# Sheet1.net
KiCad netlist of a schematic drawn in Altium Designer
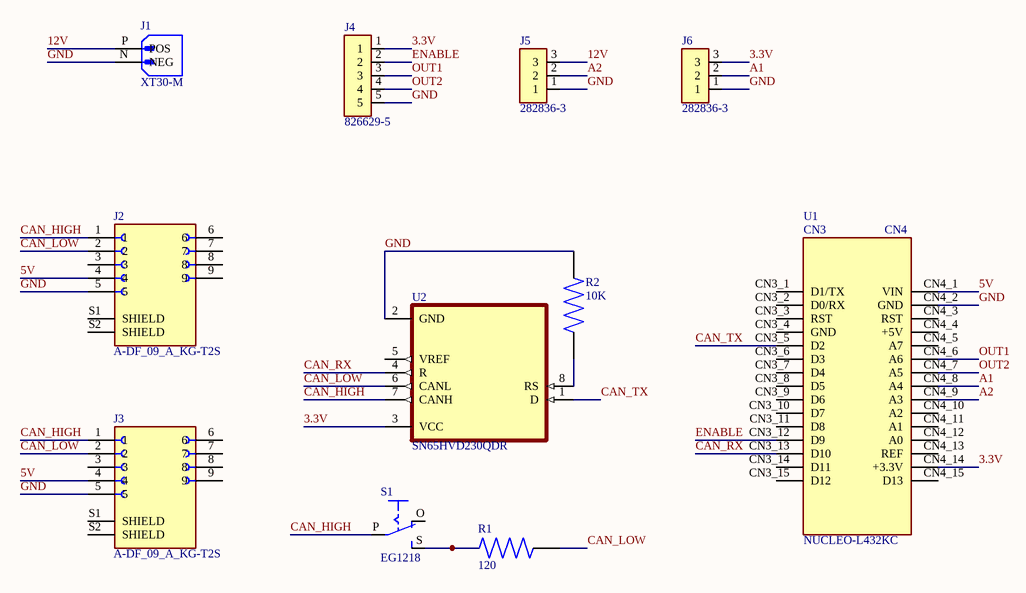
[diagram p0: Sheet1.SchDoc]

(export (version "E")
  (design (tool "Eeschema 10.0.6"))
  (components
    (comp (ref "J1")
      (value "XT30-M")
      (footprint "AMASS_XT60-M")
      (description "Plug; DC supply; XT60; male; PIN: 2; for cable; soldered; 30A; 500V")
      (fields (field (name "MP") "XT60-M") (field (name "MF") "AMASS"))
      (libsource (lib "XT30-M") (part "XT30-M"))
    )
    (comp (ref "J2")
      (value "A-DF_09_A_KG-T2S")
      (footprint "ASSMANN_A-DF_09_A_KG-T2S")
      (description "9 Position D-Sub Receptacle, Female Sockets Connector")
      (fields (field (name "MF") "Assmann WSW") (field (name "MP") "A-DF 09 A/KG-T2S"))
      (libsource (lib "A-DF_09_A_KG-T2S") (part "A-DF_09_A_KG-T2S"))
    )
    (comp (ref "J3")
      (value "A-DF_09_A_KG-T2S")
      (footprint "ASSMANN_A-DF_09_A_KG-T2S")
      (description "9 Position D-Sub Receptacle, Female Sockets Connector")
      (fields (field (name "MF") "Assmann WSW") (field (name "MP") "A-DF 09 A/KG-T2S"))
      (libsource (lib "A-DF_09_A_KG-T2S") (part "A-DF_09_A_KG-T2S"))
    )
    (comp (ref "J4")
      (value "826629-5")
      (footprint "TE_826629-5")
      (description "Board-To-Board Connector, AMPMODU MOD II Series, Through Hole, Header, 5, 2.54 mm")
      (fields (field (name "MF") "TE Connectivity"))
      (libsource (lib "826629-5") (part "826629-5"))
    )
    (comp (ref "J5")
      (value "282836-3")
      (footprint "TE_282836-3")
      (description "TERM BLOCK 3POS SIDE ENTRY 5MM")
      (libsource (lib "282836-3") (part "282836-3"))
    )
    (comp (ref "J6")
      (value "282836-3")
      (footprint "TE_282836-3")
      (description "TERM BLOCK 3POS SIDE ENTRY 5MM")
      (libsource (lib "282836-3") (part "282836-3"))
    )
    (comp (ref "R1")
      (value "120")
      (footprint "RESC3216X65N")
      (fields (field (name "MP") "KTR18EZPF9530"))
      (libsource (lib "KTR18EZPF9530") (part "KTR18EZPF9530"))
    )
    (comp (ref "R2")
      (value "10K")
      (footprint "RESC3216X65N")
      (fields (field (name "MP") "KTR18EZPF9530"))
      (libsource (lib "KTR18EZPF9530") (part "KTR18EZPF9530"))
    )
    (comp (ref "S1") (value "EG1218") (footprint "EG1218:EG1218") (libsource (lib "EG1218") (part "EG1218")))
    (comp (ref "U1")
      (value "NUCLEO-L432KC")
      (footprint "MODULE_NUCLEO-L432KC")
      (description "STM32 Nucleo-32 development board with STM32L432KC MCU, supports Arduino connectivity")
      (libsource (lib "NUCLEO-L432KC") (part "NUCLEO-L432KC"))
    )
    (comp (ref "U2")
      (value "SN65HVD230QDR")
      (footprint "SOIC127P599X175-8N")
      (description "3.3-V CAN Transceiver with Standby Mode 8-SOIC -40 to 125")
      (fields (field (name "MF") "Texas Instruments"))
      (libsource (lib "SN65HVD230QDR") (part "SN65HVD230QDR"))
    )
  )
  (nets
    (net (code "1") (name "/3.3V") (class "Default")
      (node (ref "J4") (pin "1") (pinfunction "1_1") (pintype "passive"))
      (node (ref "J6") (pin "3") (pinfunction "3_3") (pintype "passive"))
      (node (ref "U1") (pin "CN4_14") (pinfunction "+3.3V_CN4_14") (pintype "power_in"))
      (node (ref "U2") (pin "3") (pinfunction "VCC_3") (pintype "power_in"))
    )
    (net (code "2") (name "/5V") (class "Default")
      (node (ref "J2") (pin "4") (pinfunction "4_4") (pintype "passive"))
      (node (ref "J3") (pin "4") (pinfunction "4_4") (pintype "passive"))
      (node (ref "U1") (pin "CN4_1") (pinfunction "VIN_CN4_1") (pintype "power_in"))
    )
    (net (code "3") (name "/12V") (class "Default")
      (node (ref "J1") (pin "P") (pinfunction "POS_P") (pintype "passive"))
      (node (ref "J5") (pin "3") (pinfunction "3_3") (pintype "passive"))
    )
    (net (code "4") (name "/A1") (class "Default")
      (node (ref "J6") (pin "2") (pinfunction "2_2") (pintype "passive"))
      (node (ref "U1") (pin "CN4_8") (pinfunction "A4_CN4_8") (pintype "passive"))
    )
    (net (code "5") (name "/A2") (class "Default")
      (node (ref "J5") (pin "2") (pinfunction "2_2") (pintype "passive"))
      (node (ref "U1") (pin "CN4_9") (pinfunction "A3_CN4_9") (pintype "passive"))
    )
    (net (code "6") (name "/CAN_HIGH") (class "Default")
      (node (ref "J2") (pin "1") (pinfunction "1_1") (pintype "passive"))
      (node (ref "J3") (pin "1") (pinfunction "1_1") (pintype "passive"))
      (node (ref "S1") (pin "P") (pinfunction "P_P") (pintype "passive"))
      (node (ref "U2") (pin "7") (pinfunction "CANH_7") (pintype "output"))
    )
    (net (code "7") (name "/CAN_LOW") (class "Default")
      (node (ref "J2") (pin "2") (pinfunction "2_2") (pintype "passive"))
      (node (ref "J3") (pin "2") (pinfunction "2_2") (pintype "passive"))
      (node (ref "R1") (pin "2") (pinfunction "2_2") (pintype "passive"))
      (node (ref "U2") (pin "6") (pinfunction "CANL_6") (pintype "output"))
    )
    (net (code "8") (name "/CAN_RX") (class "Default")
      (node (ref "U1") (pin "CN3_13") (pinfunction "D10_CN3_13") (pintype "passive"))
      (node (ref "U2") (pin "4") (pinfunction "R_4") (pintype "output"))
    )
    (net (code "9") (name "/CAN_TX") (class "Default")
      (node (ref "U1") (pin "CN3_5") (pinfunction "D2_CN3_5") (pintype "power_in"))
      (node (ref "U2") (pin "1") (pinfunction "D_1") (pintype "input"))
    )
    (net (code "10") (name "/ENABLE") (class "Default")
      (node (ref "J4") (pin "2") (pinfunction "2_2") (pintype "passive"))
      (node (ref "U1") (pin "CN3_12") (pinfunction "D9_CN3_12") (pintype "power_in"))
    )
    (net (code "11") (name "/GND") (class "Default")
      (node (ref "J1") (pin "N") (pinfunction "NEG_N") (pintype "passive"))
      (node (ref "J2") (pin "5") (pinfunction "5_5") (pintype "passive"))
      (node (ref "J3") (pin "5") (pinfunction "5_5") (pintype "passive"))
      (node (ref "J4") (pin "5") (pinfunction "5_5") (pintype "passive"))
      (node (ref "J5") (pin "1") (pinfunction "1_1") (pintype "passive"))
      (node (ref "J6") (pin "1") (pinfunction "1_1") (pintype "passive"))
      (node (ref "R2") (pin "2") (pinfunction "2_2") (pintype "passive"))
      (node (ref "U1") (pin "CN4_2") (pinfunction "GND_CN4_2") (pintype "power_in"))
      (node (ref "U2") (pin "2") (pinfunction "GND_2") (pintype "power_in"))
    )
    (net (code "12") (name "/OUT1") (class "Default")
      (node (ref "J4") (pin "3") (pinfunction "3_3") (pintype "passive"))
      (node (ref "U1") (pin "CN4_6") (pinfunction "A6_CN4_6") (pintype "passive"))
    )
    (net (code "13") (name "/OUT2") (class "Default")
      (node (ref "J4") (pin "4") (pinfunction "4_4") (pintype "passive"))
      (node (ref "U1") (pin "CN4_7") (pinfunction "A5_CN4_7") (pintype "passive"))
    )
    (net (code "14") (name "Net-(R1-Pad1)") (class "Default")
      (node (ref "R1") (pin "1") (pinfunction "1_1") (pintype "passive"))
      (node (ref "S1") (pin "S") (pinfunction "S_S") (pintype "passive"))
    )
    (net (code "15") (name "Net-(U2-RS)") (class "Default")
      (node (ref "R2") (pin "1") (pinfunction "1_1") (pintype "passive"))
      (node (ref "U2") (pin "8") (pinfunction "RS_8") (pintype "input"))
    )
    (net (code "16") (name "unconnected-(J2-Pad3)") (class "Default")
      (node (ref "J2") (pin "3") (pinfunction "3_3") (pintype "passive"))
    )
    (net (code "17") (name "unconnected-(J2-Pad6)") (class "Default")
      (node (ref "J2") (pin "6") (pinfunction "6_6") (pintype "passive"))
    )
    (net (code "18") (name "unconnected-(J2-Pad7)") (class "Default")
      (node (ref "J2") (pin "7") (pinfunction "7_7") (pintype "passive"))
    )
    (net (code "19") (name "unconnected-(J2-Pad8)") (class "Default")
      (node (ref "J2") (pin "8") (pinfunction "8_8") (pintype "passive"))
    )
    (net (code "20") (name "unconnected-(J2-Pad9)") (class "Default")
      (node (ref "J2") (pin "9") (pinfunction "9_9") (pintype "passive"))
    )
    (net (code "21") (name "unconnected-(J2-SHIELD-PadS1)") (class "Default")
      (node (ref "J2") (pin "S1") (pinfunction "SHIELD_S1") (pintype "passive"))
    )
    (net (code "22") (name "unconnected-(J2-SHIELD-PadS2)") (class "Default")
      (node (ref "J2") (pin "S2") (pinfunction "SHIELD_S2") (pintype "passive"))
    )
    (net (code "23") (name "unconnected-(J3-Pad3)") (class "Default")
      (node (ref "J3") (pin "3") (pinfunction "3_3") (pintype "passive"))
    )
    (net (code "24") (name "unconnected-(J3-Pad6)") (class "Default")
      (node (ref "J3") (pin "6") (pinfunction "6_6") (pintype "passive"))
    )
    (net (code "25") (name "unconnected-(J3-Pad7)") (class "Default")
      (node (ref "J3") (pin "7") (pinfunction "7_7") (pintype "passive"))
    )
    (net (code "26") (name "unconnected-(J3-Pad8)") (class "Default")
      (node (ref "J3") (pin "8") (pinfunction "8_8") (pintype "passive"))
    )
    (net (code "27") (name "unconnected-(J3-Pad9)") (class "Default")
      (node (ref "J3") (pin "9") (pinfunction "9_9") (pintype "passive"))
    )
    (net (code "28") (name "unconnected-(J3-SHIELD-PadS1)") (class "Default")
      (node (ref "J3") (pin "S1") (pinfunction "SHIELD_S1") (pintype "passive"))
    )
    (net (code "29") (name "unconnected-(J3-SHIELD-PadS2)") (class "Default")
      (node (ref "J3") (pin "S2") (pinfunction "SHIELD_S2") (pintype "passive"))
    )
    (net (code "30") (name "unconnected-(S1-PadO)") (class "Default")
      (node (ref "S1") (pin "O") (pinfunction "O_O") (pintype "passive"))
    )
    (net (code "31") (name "unconnected-(U1-+5V-PadCN4_4)") (class "Default")
      (node (ref "U1") (pin "CN4_4") (pinfunction "+5V_CN4_4") (pintype "power_in"))
    )
    (net (code "32") (name "unconnected-(U1-A0-PadCN4_12)") (class "Default")
      (node (ref "U1") (pin "CN4_12") (pinfunction "A0_CN4_12") (pintype "passive"))
    )
    (net (code "33") (name "unconnected-(U1-A1-PadCN4_11)") (class "Default")
      (node (ref "U1") (pin "CN4_11") (pinfunction "A1_CN4_11") (pintype "passive"))
    )
    (net (code "34") (name "unconnected-(U1-A2-PadCN4_10)") (class "Default")
      (node (ref "U1") (pin "CN4_10") (pinfunction "A2_CN4_10") (pintype "passive"))
    )
    (net (code "35") (name "unconnected-(U1-A7-PadCN4_5)") (class "Default")
      (node (ref "U1") (pin "CN4_5") (pinfunction "A7_CN4_5") (pintype "passive"))
    )
    (net (code "36") (name "unconnected-(U1-D0{slash}RX-PadCN3_2)") (class "Default")
      (node (ref "U1") (pin "CN3_2") (pinfunction "D0/RX_CN3_2") (pintype "power_in"))
    )
    (net (code "37") (name "unconnected-(U1-D1{slash}TX-PadCN3_1)") (class "Default")
      (node (ref "U1") (pin "CN3_1") (pinfunction "D1/TX_CN3_1") (pintype "power_in"))
    )
    (net (code "38") (name "unconnected-(U1-D3-PadCN3_6)") (class "Default")
      (node (ref "U1") (pin "CN3_6") (pinfunction "D3_CN3_6") (pintype "power_in"))
    )
    (net (code "39") (name "unconnected-(U1-D4-PadCN3_7)") (class "Default")
      (node (ref "U1") (pin "CN3_7") (pinfunction "D4_CN3_7") (pintype "power_in"))
    )
    (net (code "40") (name "unconnected-(U1-D5-PadCN3_8)") (class "Default")
      (node (ref "U1") (pin "CN3_8") (pinfunction "D5_CN3_8") (pintype "power_in"))
    )
    (net (code "41") (name "unconnected-(U1-D6-PadCN3_9)") (class "Default")
      (node (ref "U1") (pin "CN3_9") (pinfunction "D6_CN3_9") (pintype "power_in"))
    )
    (net (code "42") (name "unconnected-(U1-D7-PadCN3_10)") (class "Default")
      (node (ref "U1") (pin "CN3_10") (pinfunction "D7_CN3_10") (pintype "power_in"))
    )
    (net (code "43") (name "unconnected-(U1-D8-PadCN3_11)") (class "Default")
      (node (ref "U1") (pin "CN3_11") (pinfunction "D8_CN3_11") (pintype "power_in"))
    )
    (net (code "44") (name "unconnected-(U1-D11-PadCN3_14)") (class "Default")
      (node (ref "U1") (pin "CN3_14") (pinfunction "D11_CN3_14") (pintype "power_in"))
    )
    (net (code "45") (name "unconnected-(U1-D12-PadCN3_15)") (class "Default")
      (node (ref "U1") (pin "CN3_15") (pinfunction "D12_CN3_15") (pintype "power_in"))
    )
    (net (code "46") (name "unconnected-(U1-D13-PadCN4_15)") (class "Default")
      (node (ref "U1") (pin "CN4_15") (pinfunction "D13_CN4_15") (pintype "power_in"))
    )
    (net (code "47") (name "unconnected-(U1-GND-PadCN3_4)") (class "Default")
      (node (ref "U1") (pin "CN3_4") (pinfunction "GND_CN3_4") (pintype "power_in"))
    )
    (net (code "48") (name "unconnected-(U1-REF-PadCN4_13)") (class "Default")
      (node (ref "U1") (pin "CN4_13") (pinfunction "REF_CN4_13") (pintype "passive"))
    )
    (net (code "49") (name "unconnected-(U1-RST-PadCN3_3)") (class "Default")
      (node (ref "U1") (pin "CN3_3") (pinfunction "RST_CN3_3") (pintype "power_in"))
    )
    (net (code "50") (name "unconnected-(U1-RST-PadCN4_3)") (class "Default")
      (node (ref "U1") (pin "CN4_3") (pinfunction "RST_CN4_3") (pintype "passive"))
    )
    (net (code "51") (name "unconnected-(U2-VREF-Pad5)") (class "Default")
      (node (ref "U2") (pin "5") (pinfunction "VREF_5") (pintype "output"))
    )
  )
)
